# LTC6803.net
KiCad netlist of a schematic drawn in Altium Designer
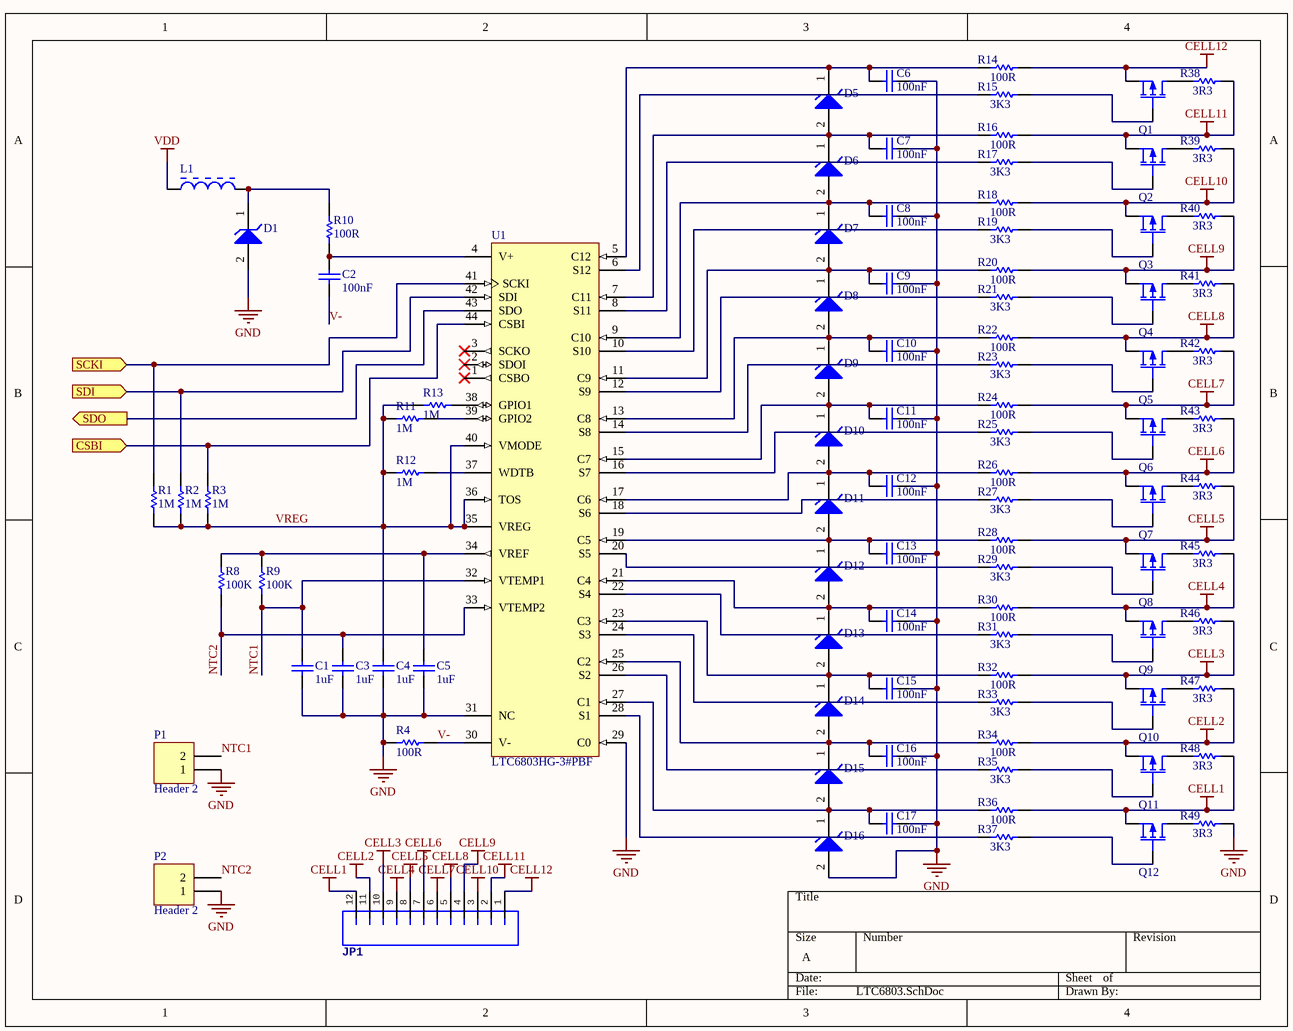
[diagram p0: LTC6803.SchDoc]

(export (version "E")
  (design (tool "Eeschema 10.0.6"))
  (components
    (comp (ref "C1")
      (value "1uF")
      (footprint "CAPC0603(1608)100_N")
      (description "CAP 1uF 6.3V Â±10% 0603 (1608 Metric) Thickness 1mm SMD")
      (fields (field (name "TOLERANCE") "Â±10%"))
      (libsource (lib "Altium Content Vault") (part "CAP"))
    )
    (comp (ref "C2")
      (value "100nF")
      (footprint "CAPC0603(1608)100_L")
      (description "CAP 100nF 100V Â±10% 0603 (1608 Metric) Thickness 1mm SMD")
      (fields (field (name "TOLERANCE") "Â±10%"))
      (libsource (lib "Altium Content Vault") (part "CAP"))
    )
    (comp (ref "C3")
      (value "1uF")
      (footprint "CAPC0603(1608)100_N")
      (description "CAP 1uF 6.3V Â±10% 0603 (1608 Metric) Thickness 1mm SMD")
      (fields (field (name "TOLERANCE") "Â±10%"))
      (libsource (lib "Altium Content Vault") (part "CAP"))
    )
    (comp (ref "C4")
      (value "1uF")
      (footprint "CAPC0603(1608)100_N")
      (description "CAP 1uF 6.3V Â±10% 0603 (1608 Metric) Thickness 1mm SMD")
      (fields (field (name "TOLERANCE") "Â±10%"))
      (libsource (lib "Altium Content Vault") (part "CAP"))
    )
    (comp (ref "C5")
      (value "1uF")
      (footprint "CAPC0603(1608)100_N")
      (description "CAP 1uF 6.3V Â±10% 0603 (1608 Metric) Thickness 1mm SMD")
      (fields (field (name "TOLERANCE") "Â±10%"))
      (libsource (lib "Altium Content Vault") (part "CAP"))
    )
    (comp (ref "C6")
      (value "100nF")
      (footprint "CAPC0603(1608)100_M")
      (description "CAP 100nF 6.3V Â±5% 0603 (1608 Metric) Thickness 1mm SMD")
      (fields (field (name "TOLERANCE") "Â±5%"))
      (libsource (lib "Altium Content Vault") (part "CAP"))
    )
    (comp (ref "C7")
      (value "100nF")
      (footprint "CAPC0603(1608)100_M")
      (description "CAP 100nF 6.3V Â±5% 0603 (1608 Metric) Thickness 1mm SMD")
      (fields (field (name "TOLERANCE") "Â±5%"))
      (libsource (lib "Altium Content Vault") (part "CAP"))
    )
    (comp (ref "C8")
      (value "100nF")
      (footprint "CAPC0603(1608)100_M")
      (description "CAP 100nF 6.3V Â±5% 0603 (1608 Metric) Thickness 1mm SMD")
      (fields (field (name "TOLERANCE") "Â±5%"))
      (libsource (lib "Altium Content Vault") (part "CAP"))
    )
    (comp (ref "C9")
      (value "100nF")
      (footprint "CAPC0603(1608)100_M")
      (description "CAP 100nF 6.3V Â±5% 0603 (1608 Metric) Thickness 1mm SMD")
      (fields (field (name "TOLERANCE") "Â±5%"))
      (libsource (lib "Altium Content Vault") (part "CAP"))
    )
    (comp (ref "C10")
      (value "100nF")
      (footprint "CAPC0603(1608)100_M")
      (description "CAP 100nF 6.3V Â±5% 0603 (1608 Metric) Thickness 1mm SMD")
      (fields (field (name "TOLERANCE") "Â±5%"))
      (libsource (lib "Altium Content Vault") (part "CAP"))
    )
    (comp (ref "C11")
      (value "100nF")
      (footprint "CAPC0603(1608)100_M")
      (description "CAP 100nF 6.3V Â±5% 0603 (1608 Metric) Thickness 1mm SMD")
      (fields (field (name "TOLERANCE") "Â±5%"))
      (libsource (lib "Altium Content Vault") (part "CAP"))
    )
    (comp (ref "C12")
      (value "100nF")
      (footprint "CAPC0603(1608)100_M")
      (description "CAP 100nF 6.3V Â±5% 0603 (1608 Metric) Thickness 1mm SMD")
      (fields (field (name "TOLERANCE") "Â±5%"))
      (libsource (lib "Altium Content Vault") (part "CAP"))
    )
    (comp (ref "C13")
      (value "100nF")
      (footprint "CAPC0603(1608)100_M")
      (description "CAP 100nF 6.3V Â±5% 0603 (1608 Metric) Thickness 1mm SMD")
      (fields (field (name "TOLERANCE") "Â±5%"))
      (libsource (lib "Altium Content Vault") (part "CAP"))
    )
    (comp (ref "C14")
      (value "100nF")
      (footprint "CAPC0603(1608)100_M")
      (description "CAP 100nF 6.3V Â±5% 0603 (1608 Metric) Thickness 1mm SMD")
      (fields (field (name "TOLERANCE") "Â±5%"))
      (libsource (lib "Altium Content Vault") (part "CAP"))
    )
    (comp (ref "C15")
      (value "100nF")
      (footprint "CAPC0603(1608)100_M")
      (description "CAP 100nF 6.3V Â±5% 0603 (1608 Metric) Thickness 1mm SMD")
      (fields (field (name "TOLERANCE") "Â±5%"))
      (libsource (lib "Altium Content Vault") (part "CAP"))
    )
    (comp (ref "C16")
      (value "100nF")
      (footprint "CAPC0603(1608)100_M")
      (description "CAP 100nF 6.3V Â±5% 0603 (1608 Metric) Thickness 1mm SMD")
      (fields (field (name "TOLERANCE") "Â±5%"))
      (libsource (lib "Altium Content Vault") (part "CAP"))
    )
    (comp (ref "C17")
      (value "100nF")
      (footprint "CAPC0603(1608)100_M")
      (description "CAP 100nF 6.3V Â±5% 0603 (1608 Metric) Thickness 1mm SMD")
      (fields (field (name "TOLERANCE") "Â±5%"))
      (libsource (lib "Altium Content Vault") (part "CAP"))
    )
    (comp (ref "D1") (value "~") (footprint "SOD-123") (libsource (lib "Components") (part "CMHZ5265B")))
    (comp (ref "D5")
      (value "~")
      (footprint "ONSC-SOD-323-2-477-02_V")
      (description "Zener Voltage Regulator, 300 mW, 2-Pin SOD-323, Tape and Reel")
      (fields (field (name "MANUFACTURER") "On Semiconductor") (field (name "PARTNUMBER") "MM3Z12VT1"))
      (libsource (lib "Altium Content Vault") (part "ONSC-K1A2-2"))
    )
    (comp (ref "D6")
      (value "~")
      (footprint "ONSC-SOD-323-2-477-02_V")
      (description "Zener Voltage Regulator, 300 mW, 2-Pin SOD-323, Tape and Reel")
      (fields (field (name "MANUFACTURER") "On Semiconductor") (field (name "PARTNUMBER") "MM3Z12VT1"))
      (libsource (lib "Altium Content Vault") (part "ONSC-K1A2-2"))
    )
    (comp (ref "D7")
      (value "~")
      (footprint "ONSC-SOD-323-2-477-02_V")
      (description "Zener Voltage Regulator, 300 mW, 2-Pin SOD-323, Tape and Reel")
      (fields (field (name "MANUFACTURER") "On Semiconductor") (field (name "PARTNUMBER") "MM3Z12VT1"))
      (libsource (lib "Altium Content Vault") (part "ONSC-K1A2-2"))
    )
    (comp (ref "D8")
      (value "~")
      (footprint "ONSC-SOD-323-2-477-02_V")
      (description "Zener Voltage Regulator, 300 mW, 2-Pin SOD-323, Tape and Reel")
      (fields (field (name "MANUFACTURER") "On Semiconductor") (field (name "PARTNUMBER") "MM3Z12VT1"))
      (libsource (lib "Altium Content Vault") (part "ONSC-K1A2-2"))
    )
    (comp (ref "D9")
      (value "~")
      (footprint "ONSC-SOD-323-2-477-02_V")
      (description "Zener Voltage Regulator, 300 mW, 2-Pin SOD-323, Tape and Reel")
      (fields (field (name "MANUFACTURER") "On Semiconductor") (field (name "PARTNUMBER") "MM3Z12VT1"))
      (libsource (lib "Altium Content Vault") (part "ONSC-K1A2-2"))
    )
    (comp (ref "D10")
      (value "~")
      (footprint "ONSC-SOD-323-2-477-02_V")
      (description "Zener Voltage Regulator, 300 mW, 2-Pin SOD-323, Tape and Reel")
      (fields (field (name "MANUFACTURER") "On Semiconductor") (field (name "PARTNUMBER") "MM3Z12VT1"))
      (libsource (lib "Altium Content Vault") (part "ONSC-K1A2-2"))
    )
    (comp (ref "D11")
      (value "~")
      (footprint "ONSC-SOD-323-2-477-02_V")
      (description "Zener Voltage Regulator, 300 mW, 2-Pin SOD-323, Tape and Reel")
      (fields (field (name "MANUFACTURER") "On Semiconductor") (field (name "PARTNUMBER") "MM3Z12VT1"))
      (libsource (lib "Altium Content Vault") (part "ONSC-K1A2-2"))
    )
    (comp (ref "D12")
      (value "~")
      (footprint "ONSC-SOD-323-2-477-02_V")
      (description "Zener Voltage Regulator, 300 mW, 2-Pin SOD-323, Tape and Reel")
      (fields (field (name "MANUFACTURER") "On Semiconductor") (field (name "PARTNUMBER") "MM3Z12VT1"))
      (libsource (lib "Altium Content Vault") (part "ONSC-K1A2-2"))
    )
    (comp (ref "D13")
      (value "~")
      (footprint "ONSC-SOD-323-2-477-02_V")
      (description "Zener Voltage Regulator, 300 mW, 2-Pin SOD-323, Tape and Reel")
      (fields (field (name "MANUFACTURER") "On Semiconductor") (field (name "PARTNUMBER") "MM3Z12VT1"))
      (libsource (lib "Altium Content Vault") (part "ONSC-K1A2-2"))
    )
    (comp (ref "D14")
      (value "~")
      (footprint "ONSC-SOD-323-2-477-02_V")
      (description "Zener Voltage Regulator, 300 mW, 2-Pin SOD-323, Tape and Reel")
      (fields (field (name "MANUFACTURER") "On Semiconductor") (field (name "PARTNUMBER") "MM3Z12VT1"))
      (libsource (lib "Altium Content Vault") (part "ONSC-K1A2-2"))
    )
    (comp (ref "D15")
      (value "~")
      (footprint "ONSC-SOD-323-2-477-02_V")
      (description "Zener Voltage Regulator, 300 mW, 2-Pin SOD-323, Tape and Reel")
      (fields (field (name "MANUFACTURER") "On Semiconductor") (field (name "PARTNUMBER") "MM3Z12VT1"))
      (libsource (lib "Altium Content Vault") (part "ONSC-K1A2-2"))
    )
    (comp (ref "D16")
      (value "~")
      (footprint "ONSC-SOD-323-2-477-02_V")
      (description "Zener Voltage Regulator, 300 mW, 2-Pin SOD-323, Tape and Reel")
      (fields (field (name "MANUFACTURER") "On Semiconductor") (field (name "PARTNUMBER") "MM3Z12VT1"))
      (libsource (lib "Altium Content Vault") (part "ONSC-K1A2-2"))
    )
    (comp (ref "JP1")
      (value "~")
      (footprint "JST-6-PTH-VERT")
      (libsource (lib "Components") (part "JST_12_RIGHT"))
    )
    (comp (ref "L1")
      (value "~")
      (footprint "MURA-BLM31-B60-CHIP-2_V3")
      (libsource (lib "Components") (part "MURA-FB-2"))
    )
    (comp (ref "P1")
      (value "Header 2")
      (footprint "HDR1X2")
      (description "Header, 2-Pin")
      (fields (field (name "PUBLISHER") "Altium Limited"))
      (libsource (lib "Miscellaneous Connectors") (part "Header 2"))
    )
    (comp (ref "P2")
      (value "Header 2")
      (footprint "HDR1X2")
      (description "Header, 2-Pin")
      (fields (field (name "PUBLISHER") "Altium Limited"))
      (libsource (lib "Miscellaneous Connectors") (part "Header 2"))
    )
    (comp (ref "Q1")
      (value "MOSFET-P")
      (footprint "SOT23-3")
      (description "P-Channel MOSFET")
      (fields (field (name "PUBLISHER") "Altium Limited"))
      (libsource (lib "Components") (part "MOSFET-P"))
    )
    (comp (ref "Q2")
      (value "MOSFET-P")
      (footprint "SOT23-3")
      (description "P-Channel MOSFET")
      (fields (field (name "PUBLISHER") "Altium Limited"))
      (libsource (lib "Components") (part "MOSFET-P"))
    )
    (comp (ref "Q3")
      (value "MOSFET-P")
      (footprint "SOT23-3")
      (description "P-Channel MOSFET")
      (fields (field (name "PUBLISHER") "Altium Limited"))
      (libsource (lib "Components") (part "MOSFET-P"))
    )
    (comp (ref "Q4")
      (value "MOSFET-P")
      (footprint "SOT23-3")
      (description "P-Channel MOSFET")
      (fields (field (name "PUBLISHER") "Altium Limited"))
      (libsource (lib "Components") (part "MOSFET-P"))
    )
    (comp (ref "Q5")
      (value "MOSFET-P")
      (footprint "SOT23-3")
      (description "P-Channel MOSFET")
      (fields (field (name "PUBLISHER") "Altium Limited"))
      (libsource (lib "Components") (part "MOSFET-P"))
    )
    (comp (ref "Q6")
      (value "MOSFET-P")
      (footprint "SOT23-3")
      (description "P-Channel MOSFET")
      (fields (field (name "PUBLISHER") "Altium Limited"))
      (libsource (lib "Components") (part "MOSFET-P"))
    )
    (comp (ref "Q7")
      (value "MOSFET-P")
      (footprint "SOT23-3")
      (description "P-Channel MOSFET")
      (fields (field (name "PUBLISHER") "Altium Limited"))
      (libsource (lib "Components") (part "MOSFET-P"))
    )
    (comp (ref "Q8")
      (value "MOSFET-P")
      (footprint "SOT23-3")
      (description "P-Channel MOSFET")
      (fields (field (name "PUBLISHER") "Altium Limited"))
      (libsource (lib "Components") (part "MOSFET-P"))
    )
    (comp (ref "Q9")
      (value "MOSFET-P")
      (footprint "SOT23-3")
      (description "P-Channel MOSFET")
      (fields (field (name "PUBLISHER") "Altium Limited"))
      (libsource (lib "Components") (part "MOSFET-P"))
    )
    (comp (ref "Q10")
      (value "MOSFET-P")
      (footprint "SOT23-3")
      (description "P-Channel MOSFET")
      (fields (field (name "PUBLISHER") "Altium Limited"))
      (libsource (lib "Components") (part "MOSFET-P"))
    )
    (comp (ref "Q11")
      (value "MOSFET-P")
      (footprint "SOT23-3")
      (description "P-Channel MOSFET")
      (fields (field (name "PUBLISHER") "Altium Limited"))
      (libsource (lib "Components") (part "MOSFET-P"))
    )
    (comp (ref "Q12")
      (value "MOSFET-P")
      (footprint "SOT23-3")
      (description "P-Channel MOSFET")
      (fields (field (name "PUBLISHER") "Altium Limited"))
      (libsource (lib "Components") (part "MOSFET-P"))
    )
    (comp (ref "R1")
      (value "1M")
      (footprint "RESC0603(1608)_L")
      (description "1M 0.1W 1% 0603 (1608 Metric)  SMD")
      (fields (field (name "POWER") "0.1 W") (field (name "TOLERANCE") "1 %"))
      (libsource (lib "Altium Content Vault") (part "RES"))
    )
    (comp (ref "R2")
      (value "1M")
      (footprint "RESC0603(1608)_L")
      (description "1M 0.1W 1% 0603 (1608 Metric)  SMD")
      (fields (field (name "POWER") "0.1 W") (field (name "TOLERANCE") "1 %"))
      (libsource (lib "Altium Content Vault") (part "RES"))
    )
    (comp (ref "R3")
      (value "1M")
      (footprint "RESC0603(1608)_L")
      (description "1M 0.1W 1% 0603 (1608 Metric)  SMD")
      (fields (field (name "POWER") "0.1 W") (field (name "TOLERANCE") "1 %"))
      (libsource (lib "Altium Content Vault") (part "RES"))
    )
    (comp (ref "R4")
      (value "100R")
      (footprint "RESC0603(1608)_L")
      (description "100R 0.1W 5% 0603 (1608 Metric)  SMD")
      (fields (field (name "TOLERANCE") "5 %") (field (name "POWER") "0.1 W"))
      (libsource (lib "Altium Content Vault") (part "RES"))
    )
    (comp (ref "R8")
      (value "100K")
      (footprint "RESC0603(1608)_N")
      (description "100K 0.1W 5% 0603 (1608 Metric)  SMD")
      (fields (field (name "TOLERANCE") "5 %") (field (name "POWER") "0.1 W"))
      (libsource (lib "Altium Content Vault") (part "RES"))
    )
    (comp (ref "R9")
      (value "100K")
      (footprint "RESC0603(1608)_N")
      (description "100K 0.1W 5% 0603 (1608 Metric)  SMD")
      (fields (field (name "TOLERANCE") "5 %") (field (name "POWER") "0.1 W"))
      (libsource (lib "Altium Content Vault") (part "RES"))
    )
    (comp (ref "R10")
      (value "100R")
      (footprint "RESC0603(1608)_L")
      (description "100R 0.1W 5% 0603 (1608 Metric)  SMD")
      (fields (field (name "TOLERANCE") "5 %") (field (name "POWER") "0.1 W"))
      (libsource (lib "Altium Content Vault") (part "CMP-1012-00050-1"))
    )
    (comp (ref "R11")
      (value "1M")
      (footprint "RESC0603(1608)_L")
      (description "1M 0.1W 1% 0603 (1608 Metric)  SMD")
      (fields (field (name "POWER") "0.1 W") (field (name "TOLERANCE") "1 %"))
      (libsource (lib "Altium Content Vault") (part "RES"))
    )
    (comp (ref "R12")
      (value "1M")
      (footprint "RESC0603(1608)_L")
      (description "1M 0.1W 1% 0603 (1608 Metric)  SMD")
      (fields (field (name "POWER") "0.1 W") (field (name "TOLERANCE") "1 %"))
      (libsource (lib "Altium Content Vault") (part "RES"))
    )
    (comp (ref "R13")
      (value "1M")
      (footprint "RESC0603(1608)_L")
      (description "1M 0.1W 1% 0603 (1608 Metric)  SMD")
      (fields (field (name "POWER") "0.1 W") (field (name "TOLERANCE") "1 %"))
      (libsource (lib "Altium Content Vault") (part "RES"))
    )
    (comp (ref "R14")
      (value "100R")
      (footprint "RESC0603(1608)_N")
      (description "100R 0.1W 5% 0603 (1608 Metric)  SMD")
      (fields (field (name "TOLERANCE") "5 %") (field (name "POWER") "0.1 W"))
      (libsource (lib "Altium Content Vault") (part "CMP-1012-00050-1"))
    )
    (comp (ref "R15")
      (value "3K3")
      (footprint "RESC0603(1608)_N")
      (description "3K3 0.1W 5% 0603 (1608 Metric)  SMD")
      (fields (field (name "TOLERANCE") "5 %") (field (name "POWER") "0.1 W"))
      (libsource (lib "Altium Content Vault") (part "RES"))
    )
    (comp (ref "R16")
      (value "100R")
      (footprint "RESC0603(1608)_N")
      (description "100R 0.1W 5% 0603 (1608 Metric)  SMD")
      (fields (field (name "TOLERANCE") "5 %") (field (name "POWER") "0.1 W"))
      (libsource (lib "Altium Content Vault") (part "CMP-1012-00050-1"))
    )
    (comp (ref "R17")
      (value "3K3")
      (footprint "RESC0603(1608)_N")
      (description "3K3 0.1W 5% 0603 (1608 Metric)  SMD")
      (fields (field (name "TOLERANCE") "5 %") (field (name "POWER") "0.1 W"))
      (libsource (lib "Altium Content Vault") (part "RES"))
    )
    (comp (ref "R18")
      (value "100R")
      (footprint "RESC0603(1608)_N")
      (description "100R 0.1W 5% 0603 (1608 Metric)  SMD")
      (fields (field (name "TOLERANCE") "5 %") (field (name "POWER") "0.1 W"))
      (libsource (lib "Altium Content Vault") (part "CMP-1012-00050-1"))
    )
    (comp (ref "R19")
      (value "3K3")
      (footprint "RESC0603(1608)_N")
      (description "3K3 0.1W 5% 0603 (1608 Metric)  SMD")
      (fields (field (name "TOLERANCE") "5 %") (field (name "POWER") "0.1 W"))
      (libsource (lib "Altium Content Vault") (part "RES"))
    )
    (comp (ref "R20")
      (value "100R")
      (footprint "RESC0603(1608)_N")
      (description "100R 0.1W 5% 0603 (1608 Metric)  SMD")
      (fields (field (name "TOLERANCE") "5 %") (field (name "POWER") "0.1 W"))
      (libsource (lib "Altium Content Vault") (part "CMP-1012-00050-1"))
    )
    (comp (ref "R21")
      (value "3K3")
      (footprint "RESC0603(1608)_N")
      (description "3K3 0.1W 5% 0603 (1608 Metric)  SMD")
      (fields (field (name "TOLERANCE") "5 %") (field (name "POWER") "0.1 W"))
      (libsource (lib "Altium Content Vault") (part "RES"))
    )
    (comp (ref "R22")
      (value "100R")
      (footprint "RESC0603(1608)_N")
      (description "100R 0.1W 5% 0603 (1608 Metric)  SMD")
      (fields (field (name "TOLERANCE") "5 %") (field (name "POWER") "0.1 W"))
      (libsource (lib "Altium Content Vault") (part "CMP-1012-00050-1"))
    )
    (comp (ref "R23")
      (value "3K3")
      (footprint "RESC0603(1608)_N")
      (description "3K3 0.1W 5% 0603 (1608 Metric)  SMD")
      (fields (field (name "TOLERANCE") "5 %") (field (name "POWER") "0.1 W"))
      (libsource (lib "Altium Content Vault") (part "RES"))
    )
    (comp (ref "R24")
      (value "100R")
      (footprint "RESC0603(1608)_N")
      (description "100R 0.1W 5% 0603 (1608 Metric)  SMD")
      (fields (field (name "TOLERANCE") "5 %") (field (name "POWER") "0.1 W"))
      (libsource (lib "Altium Content Vault") (part "CMP-1012-00050-1"))
    )
    (comp (ref "R25")
      (value "3K3")
      (footprint "RESC0603(1608)_N")
      (description "3K3 0.1W 5% 0603 (1608 Metric)  SMD")
      (fields (field (name "TOLERANCE") "5 %") (field (name "POWER") "0.1 W"))
      (libsource (lib "Altium Content Vault") (part "RES"))
    )
    (comp (ref "R26")
      (value "100R")
      (footprint "RESC0603(1608)_N")
      (description "100R 0.1W 5% 0603 (1608 Metric)  SMD")
      (fields (field (name "TOLERANCE") "5 %") (field (name "POWER") "0.1 W"))
      (libsource (lib "Altium Content Vault") (part "CMP-1012-00050-1"))
    )
    (comp (ref "R27")
      (value "3K3")
      (footprint "RESC0603(1608)_N")
      (description "3K3 0.1W 5% 0603 (1608 Metric)  SMD")
      (fields (field (name "TOLERANCE") "5 %") (field (name "POWER") "0.1 W"))
      (libsource (lib "Altium Content Vault") (part "RES"))
    )
    (comp (ref "R28")
      (value "100R")
      (footprint "RESC0603(1608)_N")
      (description "100R 0.1W 5% 0603 (1608 Metric)  SMD")
      (fields (field (name "TOLERANCE") "5 %") (field (name "POWER") "0.1 W"))
      (libsource (lib "Altium Content Vault") (part "CMP-1012-00050-1"))
    )
    (comp (ref "R29")
      (value "3K3")
      (footprint "RESC0603(1608)_N")
      (description "3K3 0.1W 5% 0603 (1608 Metric)  SMD")
      (fields (field (name "TOLERANCE") "5 %") (field (name "POWER") "0.1 W"))
      (libsource (lib "Altium Content Vault") (part "RES"))
    )
    (comp (ref "R30")
      (value "100R")
      (footprint "RESC0603(1608)_N")
      (description "100R 0.1W 5% 0603 (1608 Metric)  SMD")
      (fields (field (name "TOLERANCE") "5 %") (field (name "POWER") "0.1 W"))
      (libsource (lib "Altium Content Vault") (part "CMP-1012-00050-1"))
    )
    (comp (ref "R31")
      (value "3K3")
      (footprint "RESC0603(1608)_N")
      (description "3K3 0.1W 5% 0603 (1608 Metric)  SMD")
      (fields (field (name "TOLERANCE") "5 %") (field (name "POWER") "0.1 W"))
      (libsource (lib "Altium Content Vault") (part "RES"))
    )
    (comp (ref "R32")
      (value "100R")
      (footprint "RESC0603(1608)_N")
      (description "100R 0.1W 5% 0603 (1608 Metric)  SMD")
      (fields (field (name "TOLERANCE") "5 %") (field (name "POWER") "0.1 W"))
      (libsource (lib "Altium Content Vault") (part "CMP-1012-00050-1"))
    )
    (comp (ref "R33")
      (value "3K3")
      (footprint "RESC0603(1608)_N")
      (description "3K3 0.1W 5% 0603 (1608 Metric)  SMD")
      (fields (field (name "TOLERANCE") "5 %") (field (name "POWER") "0.1 W"))
      (libsource (lib "Altium Content Vault") (part "RES"))
    )
    (comp (ref "R34")
      (value "100R")
      (footprint "RESC0603(1608)_N")
      (description "100R 0.1W 5% 0603 (1608 Metric)  SMD")
      (fields (field (name "TOLERANCE") "5 %") (field (name "POWER") "0.1 W"))
      (libsource (lib "Altium Content Vault") (part "CMP-1012-00050-1"))
    )
    (comp (ref "R35")
      (value "3K3")
      (footprint "RESC0603(1608)_N")
      (description "3K3 0.1W 5% 0603 (1608 Metric)  SMD")
      (fields (field (name "TOLERANCE") "5 %") (field (name "POWER") "0.1 W"))
      (libsource (lib "Altium Content Vault") (part "RES"))
    )
    (comp (ref "R36")
      (value "100R")
      (footprint "RESC0603(1608)_N")
      (description "100R 0.1W 5% 0603 (1608 Metric)  SMD")
      (fields (field (name "TOLERANCE") "5 %") (field (name "POWER") "0.1 W"))
      (libsource (lib "Altium Content Vault") (part "CMP-1012-00050-1"))
    )
    (comp (ref "R37")
      (value "3K3")
      (footprint "RESC0603(1608)_N")
      (description "3K3 0.1W 5% 0603 (1608 Metric)  SMD")
      (fields (field (name "TOLERANCE") "5 %") (field (name "POWER") "0.1 W"))
      (libsource (lib "Altium Content Vault") (part "RES"))
    )
    (comp (ref "R38")
      (value "3R3")
      (footprint "RESC2512(6432)_N")
      (description "3R3 1W 5% 2512 (6432 Metric)  SMD")
      (fields (field (name "TOLERANCE") "5 %") (field (name "POWER") "1 W"))
      (libsource (lib "Altium Content Vault") (part "RES"))
    )
    (comp (ref "R39")
      (value "3R3")
      (footprint "RESC2512(6432)_N")
      (description "3R3 1W 5% 2512 (6432 Metric)  SMD")
      (fields (field (name "TOLERANCE") "5 %") (field (name "POWER") "1 W"))
      (libsource (lib "Altium Content Vault") (part "RES"))
    )
    (comp (ref "R40")
      (value "3R3")
      (footprint "RESC2512(6432)_N")
      (description "3R3 1W 5% 2512 (6432 Metric)  SMD")
      (fields (field (name "TOLERANCE") "5 %") (field (name "POWER") "1 W"))
      (libsource (lib "Altium Content Vault") (part "RES"))
    )
    (comp (ref "R41")
      (value "3R3")
      (footprint "RESC2512(6432)_N")
      (description "3R3 1W 5% 2512 (6432 Metric)  SMD")
      (fields (field (name "TOLERANCE") "5 %") (field (name "POWER") "1 W"))
      (libsource (lib "Altium Content Vault") (part "RES"))
    )
    (comp (ref "R42")
      (value "3R3")
      (footprint "RESC2512(6432)_N")
      (description "3R3 1W 5% 2512 (6432 Metric)  SMD")
      (fields (field (name "TOLERANCE") "5 %") (field (name "POWER") "1 W"))
      (libsource (lib "Altium Content Vault") (part "RES"))
    )
    (comp (ref "R43")
      (value "3R3")
      (footprint "RESC2512(6432)_N")
      (description "3R3 1W 5% 2512 (6432 Metric)  SMD")
      (fields (field (name "TOLERANCE") "5 %") (field (name "POWER") "1 W"))
      (libsource (lib "Altium Content Vault") (part "RES"))
    )
    (comp (ref "R44")
      (value "3R3")
      (footprint "RESC2512(6432)_N")
      (description "3R3 1W 5% 2512 (6432 Metric)  SMD")
      (fields (field (name "TOLERANCE") "5 %") (field (name "POWER") "1 W"))
      (libsource (lib "Altium Content Vault") (part "RES"))
    )
    (comp (ref "R45")
      (value "3R3")
      (footprint "RESC2512(6432)_N")
      (description "3R3 1W 5% 2512 (6432 Metric)  SMD")
      (fields (field (name "TOLERANCE") "5 %") (field (name "POWER") "1 W"))
      (libsource (lib "Altium Content Vault") (part "RES"))
    )
    (comp (ref "R46")
      (value "3R3")
      (footprint "RESC2512(6432)_N")
      (description "3R3 1W 5% 2512 (6432 Metric)  SMD")
      (fields (field (name "TOLERANCE") "5 %") (field (name "POWER") "1 W"))
      (libsource (lib "Altium Content Vault") (part "RES"))
    )
    (comp (ref "R47")
      (value "3R3")
      (footprint "RESC2512(6432)_N")
      (description "3R3 1W 5% 2512 (6432 Metric)  SMD")
      (fields (field (name "TOLERANCE") "5 %") (field (name "POWER") "1 W"))
      (libsource (lib "Altium Content Vault") (part "RES"))
    )
    (comp (ref "R48")
      (value "3R3")
      (footprint "RESC2512(6432)_N")
      (description "3R3 1W 5% 2512 (6432 Metric)  SMD")
      (fields (field (name "TOLERANCE") "5 %") (field (name "POWER") "1 W"))
      (libsource (lib "Altium Content Vault") (part "RES"))
    )
    (comp (ref "R49")
      (value "3R3")
      (footprint "RESC2512(6432)_N")
      (description "3R3 1W 5% 2512 (6432 Metric)  SMD")
      (fields (field (name "TOLERANCE") "5 %") (field (name "POWER") "1 W"))
      (libsource (lib "Altium Content Vault") (part "RES"))
    )
    (comp (ref "U1")
      (value "LTC6803HG-3#PBF")
      (footprint "LT-G-44_L")
      (description "Multicell Battery Stack Monitor, 60 V Vin MAX, 44-pin SOP (G-44), -40 to 125 degC, Pb-Free")
      (fields (field (name "MANUFACTURER") "Linear Technology"))
      (libsource (lib "Altium Content Vault") (part "LT-LTC6803-3-G-44"))
    )
  )
  (nets
    (net (code "1") (name "/CSBI") (class "Default")
      (node (ref "R3") (pin "2") (pinfunction "2_2") (pintype "passive"))
      (node (ref "U1") (pin "44") (pinfunction "CSBI_44") (pintype "input"))
    )
    (net (code "2") (name "/NTC1") (class "Default")
      (node (ref "C1") (pin "2") (pinfunction "2_2") (pintype "passive"))
      (node (ref "P1") (pin "2") (pinfunction "2_2") (pintype "passive"))
      (node (ref "R9") (pin "1") (pinfunction "1_1") (pintype "passive"))
      (node (ref "U1") (pin "32") (pinfunction "VTEMP1_32") (pintype "input"))
    )
    (net (code "3") (name "/NTC2") (class "Default")
      (node (ref "C3") (pin "2") (pinfunction "2_2") (pintype "passive"))
      (node (ref "P2") (pin "2") (pinfunction "2_2") (pintype "passive"))
      (node (ref "R8") (pin "1") (pinfunction "1_1") (pintype "passive"))
      (node (ref "U1") (pin "33") (pinfunction "VTEMP2_33") (pintype "input"))
    )
    (net (code "4") (name "/SCKI") (class "Default")
      (node (ref "R1") (pin "2") (pinfunction "2_2") (pintype "passive"))
      (node (ref "U1") (pin "41") (pinfunction "SCKI_41") (pintype "input"))
    )
    (net (code "5") (name "/SDI") (class "Default")
      (node (ref "R2") (pin "2") (pinfunction "2_2") (pintype "passive"))
      (node (ref "U1") (pin "42") (pinfunction "SDI_42") (pintype "input"))
    )
    (net (code "6") (name "/SDO") (class "Default")
      (node (ref "U1") (pin "43") (pinfunction "SDO_43") (pintype "open_collector"))
    )
    (net (code "7") (name "/V-") (class "Default")
      (node (ref "C2") (pin "1") (pinfunction "1_1") (pintype "passive"))
      (node (ref "R4") (pin "2") (pinfunction "2_2") (pintype "passive"))
      (node (ref "U1") (pin "30") (pinfunction "V-_30") (pintype "power_in"))
    )
    (net (code "8") (name "/VREG") (class "Default")
      (node (ref "C4") (pin "2") (pinfunction "2_2") (pintype "passive"))
      (node (ref "R1") (pin "1") (pinfunction "1_1") (pintype "passive"))
      (node (ref "R11") (pin "1") (pinfunction "1_1") (pintype "passive"))
      (node (ref "R12") (pin "1") (pinfunction "1_1") (pintype "passive"))
      (node (ref "R13") (pin "1") (pinfunction "1_1") (pintype "passive"))
      (node (ref "R2") (pin "1") (pinfunction "1_1") (pintype "passive"))
      (node (ref "R3") (pin "1") (pinfunction "1_1") (pintype "passive"))
      (node (ref "U1") (pin "35") (pinfunction "VREG_35") (pintype "power_in"))
      (node (ref "U1") (pin "36") (pinfunction "TOS_36") (pintype "input"))
      (node (ref "U1") (pin "40") (pinfunction "VMODE_40") (pintype "input"))
    )
    (net (code "9") (name "CELL1") (class "Default")
      (node (ref "JP1") (pin "12") (pinfunction "12_12") (pintype "passive"))
      (node (ref "Q12") (pin "3") (pinfunction "S_3") (pintype "passive"))
      (node (ref "R36") (pin "2") (pinfunction "2_2") (pintype "passive"))
      (node (ref "R48") (pin "1") (pinfunction "1_1") (pintype "passive"))
    )
    (net (code "10") (name "CELL2") (class "Default")
      (node (ref "JP1") (pin "11") (pinfunction "11_11") (pintype "passive"))
      (node (ref "Q11") (pin "3") (pinfunction "S_3") (pintype "passive"))
      (node (ref "R34") (pin "2") (pinfunction "2_2") (pintype "passive"))
      (node (ref "R47") (pin "1") (pinfunction "1_1") (pintype "passive"))
    )
    (net (code "11") (name "CELL3") (class "Default")
      (node (ref "JP1") (pin "10") (pinfunction "10_10") (pintype "passive"))
      (node (ref "Q10") (pin "3") (pinfunction "S_3") (pintype "passive"))
      (node (ref "R32") (pin "2") (pinfunction "2_2") (pintype "passive"))
      (node (ref "R46") (pin "1") (pinfunction "1_1") (pintype "passive"))
    )
    (net (code "12") (name "CELL4") (class "Default")
      (node (ref "JP1") (pin "9") (pinfunction "9_9") (pintype "passive"))
      (node (ref "Q9") (pin "3") (pinfunction "S_3") (pintype "passive"))
      (node (ref "R30") (pin "2") (pinfunction "2_2") (pintype "passive"))
      (node (ref "R45") (pin "1") (pinfunction "1_1") (pintype "passive"))
    )
    (net (code "13") (name "CELL5") (class "Default")
      (node (ref "JP1") (pin "8") (pinfunction "8_8") (pintype "passive"))
      (node (ref "Q8") (pin "3") (pinfunction "S_3") (pintype "passive"))
      (node (ref "R28") (pin "2") (pinfunction "2_2") (pintype "passive"))
      (node (ref "R44") (pin "1") (pinfunction "1_1") (pintype "passive"))
    )
    (net (code "14") (name "CELL6") (class "Default")
      (node (ref "JP1") (pin "7") (pinfunction "7_7") (pintype "passive"))
      (node (ref "Q7") (pin "3") (pinfunction "S_3") (pintype "passive"))
      (node (ref "R26") (pin "2") (pinfunction "2_2") (pintype "passive"))
      (node (ref "R43") (pin "1") (pinfunction "1_1") (pintype "passive"))
    )
    (net (code "15") (name "CELL7") (class "Default")
      (node (ref "JP1") (pin "6") (pinfunction "6_6") (pintype "passive"))
      (node (ref "Q6") (pin "3") (pinfunction "S_3") (pintype "passive"))
      (node (ref "R24") (pin "2") (pinfunction "2_2") (pintype "passive"))
      (node (ref "R42") (pin "1") (pinfunction "1_1") (pintype "passive"))
    )
    (net (code "16") (name "CELL8") (class "Default")
      (node (ref "JP1") (pin "5") (pinfunction "5_5") (pintype "passive"))
      (node (ref "Q5") (pin "3") (pinfunction "S_3") (pintype "passive"))
      (node (ref "R22") (pin "2") (pinfunction "2_2") (pintype "passive"))
      (node (ref "R41") (pin "1") (pinfunction "1_1") (pintype "passive"))
    )
    (net (code "17") (name "CELL9") (class "Default")
      (node (ref "JP1") (pin "4") (pinfunction "4_4") (pintype "passive"))
      (node (ref "Q4") (pin "3") (pinfunction "S_3") (pintype "passive"))
      (node (ref "R20") (pin "2") (pinfunction "2_2") (pintype "passive"))
      (node (ref "R40") (pin "1") (pinfunction "1_1") (pintype "passive"))
    )
    (net (code "18") (name "CELL10") (class "Default")
      (node (ref "JP1") (pin "3") (pinfunction "3_3") (pintype "passive"))
      (node (ref "Q3") (pin "3") (pinfunction "S_3") (pintype "passive"))
      (node (ref "R18") (pin "2") (pinfunction "2_2") (pintype "passive"))
      (node (ref "R39") (pin "1") (pinfunction "1_1") (pintype "passive"))
    )
    (net (code "19") (name "CELL11") (class "Default")
      (node (ref "JP1") (pin "2") (pinfunction "2_2") (pintype "passive"))
      (node (ref "Q2") (pin "3") (pinfunction "S_3") (pintype "passive"))
      (node (ref "R16") (pin "2") (pinfunction "2_2") (pintype "passive"))
      (node (ref "R38") (pin "1") (pinfunction "1_1") (pintype "passive"))
    )
    (net (code "20") (name "CELL12") (class "Default")
      (node (ref "JP1") (pin "1") (pinfunction "1_1") (pintype "passive"))
      (node (ref "Q1") (pin "3") (pinfunction "S_3") (pintype "passive"))
      (node (ref "R14") (pin "2") (pinfunction "2_2") (pintype "passive"))
    )
    (net (code "21") (name "GND") (class "Default")
      (node (ref "C1") (pin "1") (pinfunction "1_1") (pintype "passive"))
      (node (ref "C10") (pin "1") (pinfunction "1_1") (pintype "passive"))
      (node (ref "C11") (pin "1") (pinfunction "1_1") (pintype "passive"))
      (node (ref "C12") (pin "1") (pinfunction "1_1") (pintype "passive"))
      (node (ref "C13") (pin "1") (pinfunction "1_1") (pintype "passive"))
      (node (ref "C14") (pin "1") (pinfunction "1_1") (pintype "passive"))
      (node (ref "C15") (pin "1") (pinfunction "1_1") (pintype "passive"))
      (node (ref "C16") (pin "1") (pinfunction "1_1") (pintype "passive"))
      (node (ref "C17") (pin "1") (pinfunction "1_1") (pintype "passive"))
      (node (ref "C3") (pin "1") (pinfunction "1_1") (pintype "passive"))
      (node (ref "C4") (pin "1") (pinfunction "1_1") (pintype "passive"))
      (node (ref "C5") (pin "1") (pinfunction "1_1") (pintype "passive"))
      (node (ref "C6") (pin "1") (pinfunction "1_1") (pintype "passive"))
      (node (ref "C7") (pin "1") (pinfunction "1_1") (pintype "passive"))
      (node (ref "C8") (pin "1") (pinfunction "1_1") (pintype "passive"))
      (node (ref "C9") (pin "1") (pinfunction "1_1") (pintype "passive"))
      (node (ref "D1") (pin "2") (pinfunction "A_2") (pintype "passive"))
      (node (ref "D16") (pin "2") (pinfunction "A_2") (pintype "passive"))
      (node (ref "P1") (pin "1") (pinfunction "1_1") (pintype "passive"))
      (node (ref "P2") (pin "1") (pinfunction "1_1") (pintype "passive"))
      (node (ref "R4") (pin "1") (pinfunction "1_1") (pintype "passive"))
      (node (ref "R49") (pin "1") (pinfunction "1_1") (pintype "passive"))
      (node (ref "U1") (pin "29") (pinfunction "C0_29") (pintype "input"))
      (node (ref "U1") (pin "31") (pinfunction "NC_31") (pintype "passive"))
    )
    (net (code "22") (name "Net-(D1-K)") (class "Default")
      (node (ref "D1") (pin "1") (pinfunction "K_1") (pintype "passive"))
      (node (ref "L1") (pin "2") (pinfunction "2_2") (pintype "passive"))
      (node (ref "R10") (pin "2") (pinfunction "2_2") (pintype "passive"))
    )
    (net (code "23") (name "Net-(D5-A)") (class "Default")
      (node (ref "C7") (pin "2") (pinfunction "2_2") (pintype "passive"))
      (node (ref "D5") (pin "2") (pinfunction "A_2") (pintype "passive"))
      (node (ref "D6") (pin "1") (pinfunction "K_1") (pintype "passive"))
      (node (ref "R16") (pin "1") (pinfunction "1_1") (pintype "passive"))
      (node (ref "U1") (pin "7") (pinfunction "C11_7") (pintype "input"))
    )
    (net (code "24") (name "Net-(D5-K)") (class "Default")
      (node (ref "C6") (pin "2") (pinfunction "2_2") (pintype "passive"))
      (node (ref "D5") (pin "1") (pinfunction "K_1") (pintype "passive"))
      (node (ref "R14") (pin "1") (pinfunction "1_1") (pintype "passive"))
      (node (ref "U1") (pin "5") (pinfunction "C12_5") (pintype "input"))
    )
    (net (code "25") (name "Net-(D6-A)") (class "Default")
      (node (ref "C8") (pin "2") (pinfunction "2_2") (pintype "passive"))
      (node (ref "D6") (pin "2") (pinfunction "A_2") (pintype "passive"))
      (node (ref "D7") (pin "1") (pinfunction "K_1") (pintype "passive"))
      (node (ref "R18") (pin "1") (pinfunction "1_1") (pintype "passive"))
      (node (ref "U1") (pin "9") (pinfunction "C10_9") (pintype "input"))
    )
    (net (code "26") (name "Net-(D7-A)") (class "Default")
      (node (ref "C9") (pin "2") (pinfunction "2_2") (pintype "passive"))
      (node (ref "D7") (pin "2") (pinfunction "A_2") (pintype "passive"))
      (node (ref "D8") (pin "1") (pinfunction "K_1") (pintype "passive"))
      (node (ref "R20") (pin "1") (pinfunction "1_1") (pintype "passive"))
      (node (ref "U1") (pin "11") (pinfunction "C9_11") (pintype "input"))
    )
    (net (code "27") (name "Net-(D8-A)") (class "Default")
      (node (ref "C10") (pin "2") (pinfunction "2_2") (pintype "passive"))
      (node (ref "D8") (pin "2") (pinfunction "A_2") (pintype "passive"))
      (node (ref "D9") (pin "1") (pinfunction "K_1") (pintype "passive"))
      (node (ref "R22") (pin "1") (pinfunction "1_1") (pintype "passive"))
      (node (ref "U1") (pin "13") (pinfunction "C8_13") (pintype "input"))
    )
    (net (code "28") (name "Net-(D10-A)") (class "Default")
      (node (ref "C12") (pin "2") (pinfunction "2_2") (pintype "passive"))
      (node (ref "D10") (pin "2") (pinfunction "A_2") (pintype "passive"))
      (node (ref "D11") (pin "1") (pinfunction "K_1") (pintype "passive"))
      (node (ref "R26") (pin "1") (pinfunction "1_1") (pintype "passive"))
      (node (ref "U1") (pin "17") (pinfunction "C6_17") (pintype "input"))
    )
    (net (code "29") (name "Net-(D10-K)") (class "Default")
      (node (ref "C11") (pin "2") (pinfunction "2_2") (pintype "passive"))
      (node (ref "D10") (pin "1") (pinfunction "K_1") (pintype "passive"))
      (node (ref "D9") (pin "2") (pinfunction "A_2") (pintype "passive"))
      (node (ref "R24") (pin "1") (pinfunction "1_1") (pintype "passive"))
      (node (ref "U1") (pin "15") (pinfunction "C7_15") (pintype "input"))
    )
    (net (code "30") (name "Net-(D11-A)") (class "Default")
      (node (ref "C13") (pin "2") (pinfunction "2_2") (pintype "passive"))
      (node (ref "D11") (pin "2") (pinfunction "A_2") (pintype "passive"))
      (node (ref "D12") (pin "1") (pinfunction "K_1") (pintype "passive"))
      (node (ref "R28") (pin "1") (pinfunction "1_1") (pintype "passive"))
      (node (ref "U1") (pin "19") (pinfunction "C5_19") (pintype "input"))
    )
    (net (code "31") (name "Net-(D12-A)") (class "Default")
      (node (ref "C14") (pin "2") (pinfunction "2_2") (pintype "passive"))
      (node (ref "D12") (pin "2") (pinfunction "A_2") (pintype "passive"))
      (node (ref "D13") (pin "1") (pinfunction "K_1") (pintype "passive"))
      (node (ref "R30") (pin "1") (pinfunction "1_1") (pintype "passive"))
      (node (ref "U1") (pin "21") (pinfunction "C4_21") (pintype "input"))
    )
    (net (code "32") (name "Net-(D13-A)") (class "Default")
      (node (ref "C15") (pin "2") (pinfunction "2_2") (pintype "passive"))
      (node (ref "D13") (pin "2") (pinfunction "A_2") (pintype "passive"))
      (node (ref "D14") (pin "1") (pinfunction "K_1") (pintype "passive"))
      (node (ref "R32") (pin "1") (pinfunction "1_1") (pintype "passive"))
      (node (ref "U1") (pin "23") (pinfunction "C3_23") (pintype "input"))
    )
    (net (code "33") (name "Net-(D14-A)") (class "Default")
      (node (ref "C16") (pin "2") (pinfunction "2_2") (pintype "passive"))
      (node (ref "D14") (pin "2") (pinfunction "A_2") (pintype "passive"))
      (node (ref "D15") (pin "1") (pinfunction "K_1") (pintype "passive"))
      (node (ref "R34") (pin "1") (pinfunction "1_1") (pintype "passive"))
      (node (ref "U1") (pin "25") (pinfunction "C2_25") (pintype "input"))
    )
    (net (code "34") (name "Net-(D15-A)") (class "Default")
      (node (ref "C17") (pin "2") (pinfunction "2_2") (pintype "passive"))
      (node (ref "D15") (pin "2") (pinfunction "A_2") (pintype "passive"))
      (node (ref "D16") (pin "1") (pinfunction "K_1") (pintype "passive"))
      (node (ref "R36") (pin "1") (pinfunction "1_1") (pintype "passive"))
      (node (ref "U1") (pin "27") (pinfunction "C1_27") (pintype "input"))
    )
    (net (code "35") (name "Net-(Q1-D)") (class "Default")
      (node (ref "Q1") (pin "2") (pinfunction "D_2") (pintype "passive"))
      (node (ref "R38") (pin "2") (pinfunction "2_2") (pintype "passive"))
    )
    (net (code "36") (name "Net-(Q1-G)") (class "Default")
      (node (ref "Q1") (pin "1") (pinfunction "G_1") (pintype "passive"))
      (node (ref "R15") (pin "2") (pinfunction "2_2") (pintype "passive"))
    )
    (net (code "37") (name "Net-(Q2-D)") (class "Default")
      (node (ref "Q2") (pin "2") (pinfunction "D_2") (pintype "passive"))
      (node (ref "R39") (pin "2") (pinfunction "2_2") (pintype "passive"))
    )
    (net (code "38") (name "Net-(Q2-G)") (class "Default")
      (node (ref "Q2") (pin "1") (pinfunction "G_1") (pintype "passive"))
      (node (ref "R17") (pin "2") (pinfunction "2_2") (pintype "passive"))
    )
    (net (code "39") (name "Net-(Q3-D)") (class "Default")
      (node (ref "Q3") (pin "2") (pinfunction "D_2") (pintype "passive"))
      (node (ref "R40") (pin "2") (pinfunction "2_2") (pintype "passive"))
    )
    (net (code "40") (name "Net-(Q3-G)") (class "Default")
      (node (ref "Q3") (pin "1") (pinfunction "G_1") (pintype "passive"))
      (node (ref "R19") (pin "2") (pinfunction "2_2") (pintype "passive"))
    )
    (net (code "41") (name "Net-(Q4-D)") (class "Default")
      (node (ref "Q4") (pin "2") (pinfunction "D_2") (pintype "passive"))
      (node (ref "R41") (pin "2") (pinfunction "2_2") (pintype "passive"))
    )
    (net (code "42") (name "Net-(Q4-G)") (class "Default")
      (node (ref "Q4") (pin "1") (pinfunction "G_1") (pintype "passive"))
      (node (ref "R21") (pin "2") (pinfunction "2_2") (pintype "passive"))
    )
    (net (code "43") (name "Net-(Q5-D)") (class "Default")
      (node (ref "Q5") (pin "2") (pinfunction "D_2") (pintype "passive"))
      (node (ref "R42") (pin "2") (pinfunction "2_2") (pintype "passive"))
    )
    (net (code "44") (name "Net-(Q5-G)") (class "Default")
      (node (ref "Q5") (pin "1") (pinfunction "G_1") (pintype "passive"))
      (node (ref "R23") (pin "2") (pinfunction "2_2") (pintype "passive"))
    )
    (net (code "45") (name "Net-(Q6-D)") (class "Default")
      (node (ref "Q6") (pin "2") (pinfunction "D_2") (pintype "passive"))
      (node (ref "R43") (pin "2") (pinfunction "2_2") (pintype "passive"))
    )
    (net (code "46") (name "Net-(Q6-G)") (class "Default")
      (node (ref "Q6") (pin "1") (pinfunction "G_1") (pintype "passive"))
      (node (ref "R25") (pin "2") (pinfunction "2_2") (pintype "passive"))
    )
    (net (code "47") (name "Net-(Q7-D)") (class "Default")
      (node (ref "Q7") (pin "2") (pinfunction "D_2") (pintype "passive"))
      (node (ref "R44") (pin "2") (pinfunction "2_2") (pintype "passive"))
    )
    (net (code "48") (name "Net-(Q7-G)") (class "Default")
      (node (ref "Q7") (pin "1") (pinfunction "G_1") (pintype "passive"))
      (node (ref "R27") (pin "2") (pinfunction "2_2") (pintype "passive"))
    )
    (net (code "49") (name "Net-(Q8-D)") (class "Default")
      (node (ref "Q8") (pin "2") (pinfunction "D_2") (pintype "passive"))
      (node (ref "R45") (pin "2") (pinfunction "2_2") (pintype "passive"))
    )
    (net (code "50") (name "Net-(Q8-G)") (class "Default")
      (node (ref "Q8") (pin "1") (pinfunction "G_1") (pintype "passive"))
      (node (ref "R29") (pin "2") (pinfunction "2_2") (pintype "passive"))
    )
    (net (code "51") (name "Net-(Q9-D)") (class "Default")
      (node (ref "Q9") (pin "2") (pinfunction "D_2") (pintype "passive"))
      (node (ref "R46") (pin "2") (pinfunction "2_2") (pintype "passive"))
    )
    (net (code "52") (name "Net-(Q9-G)") (class "Default")
      (node (ref "Q9") (pin "1") (pinfunction "G_1") (pintype "passive"))
      (node (ref "R31") (pin "2") (pinfunction "2_2") (pintype "passive"))
    )
    (net (code "53") (name "Net-(Q10-D)") (class "Default")
      (node (ref "Q10") (pin "2") (pinfunction "D_2") (pintype "passive"))
      (node (ref "R47") (pin "2") (pinfunction "2_2") (pintype "passive"))
    )
    (net (code "54") (name "Net-(Q10-G)") (class "Default")
      (node (ref "Q10") (pin "1") (pinfunction "G_1") (pintype "passive"))
      (node (ref "R33") (pin "2") (pinfunction "2_2") (pintype "passive"))
    )
    (net (code "55") (name "Net-(Q11-D)") (class "Default")
      (node (ref "Q11") (pin "2") (pinfunction "D_2") (pintype "passive"))
      (node (ref "R48") (pin "2") (pinfunction "2_2") (pintype "passive"))
    )
    (net (code "56") (name "Net-(Q11-G)") (class "Default")
      (node (ref "Q11") (pin "1") (pinfunction "G_1") (pintype "passive"))
      (node (ref "R35") (pin "2") (pinfunction "2_2") (pintype "passive"))
    )
    (net (code "57") (name "Net-(Q12-D)") (class "Default")
      (node (ref "Q12") (pin "2") (pinfunction "D_2") (pintype "passive"))
      (node (ref "R49") (pin "2") (pinfunction "2_2") (pintype "passive"))
    )
    (net (code "58") (name "Net-(Q12-G)") (class "Default")
      (node (ref "Q12") (pin "1") (pinfunction "G_1") (pintype "passive"))
      (node (ref "R37") (pin "2") (pinfunction "2_2") (pintype "passive"))
    )
    (net (code "59") (name "Net-(U1-GPIO1)") (class "Default")
      (node (ref "R13") (pin "2") (pinfunction "2_2") (pintype "passive"))
      (node (ref "U1") (pin "38") (pinfunction "GPIO1_38") (pintype "bidirectional"))
    )
    (net (code "60") (name "Net-(U1-GPIO2)") (class "Default")
      (node (ref "R11") (pin "2") (pinfunction "2_2") (pintype "passive"))
      (node (ref "U1") (pin "39") (pinfunction "GPIO2_39") (pintype "bidirectional"))
    )
    (net (code "61") (name "Net-(U1-S1)") (class "Default")
      (node (ref "R37") (pin "1") (pinfunction "1_1") (pintype "passive"))
      (node (ref "U1") (pin "28") (pinfunction "S1_28") (pintype "tri_state"))
    )
    (net (code "62") (name "Net-(U1-S2)") (class "Default")
      (node (ref "R35") (pin "1") (pinfunction "1_1") (pintype "passive"))
      (node (ref "U1") (pin "26") (pinfunction "S2_26") (pintype "tri_state"))
    )
    (net (code "63") (name "Net-(U1-S3)") (class "Default")
      (node (ref "R33") (pin "1") (pinfunction "1_1") (pintype "passive"))
      (node (ref "U1") (pin "24") (pinfunction "S3_24") (pintype "tri_state"))
    )
    (net (code "64") (name "Net-(U1-S4)") (class "Default")
      (node (ref "R31") (pin "1") (pinfunction "1_1") (pintype "passive"))
      (node (ref "U1") (pin "22") (pinfunction "S4_22") (pintype "tri_state"))
    )
    (net (code "65") (name "Net-(U1-S5)") (class "Default")
      (node (ref "R29") (pin "1") (pinfunction "1_1") (pintype "passive"))
      (node (ref "U1") (pin "20") (pinfunction "S5_20") (pintype "tri_state"))
    )
    (net (code "66") (name "Net-(U1-S6)") (class "Default")
      (node (ref "R27") (pin "1") (pinfunction "1_1") (pintype "passive"))
      (node (ref "U1") (pin "18") (pinfunction "S6_18") (pintype "tri_state"))
    )
    (net (code "67") (name "Net-(U1-S7)") (class "Default")
      (node (ref "R25") (pin "1") (pinfunction "1_1") (pintype "passive"))
      (node (ref "U1") (pin "16") (pinfunction "S7_16") (pintype "tri_state"))
    )
    (net (code "68") (name "Net-(U1-S8)") (class "Default")
      (node (ref "R23") (pin "1") (pinfunction "1_1") (pintype "passive"))
      (node (ref "U1") (pin "14") (pinfunction "S8_14") (pintype "tri_state"))
    )
    (net (code "69") (name "Net-(U1-S9)") (class "Default")
      (node (ref "R21") (pin "1") (pinfunction "1_1") (pintype "passive"))
      (node (ref "U1") (pin "12") (pinfunction "S9_12") (pintype "tri_state"))
    )
    (net (code "70") (name "Net-(U1-S10)") (class "Default")
      (node (ref "R19") (pin "1") (pinfunction "1_1") (pintype "passive"))
      (node (ref "U1") (pin "10") (pinfunction "S10_10") (pintype "tri_state"))
    )
    (net (code "71") (name "Net-(U1-S11)") (class "Default")
      (node (ref "R17") (pin "1") (pinfunction "1_1") (pintype "passive"))
      (node (ref "U1") (pin "8") (pinfunction "S11_8") (pintype "tri_state"))
    )
    (net (code "72") (name "Net-(U1-S12)") (class "Default")
      (node (ref "R15") (pin "1") (pinfunction "1_1") (pintype "passive"))
      (node (ref "U1") (pin "6") (pinfunction "S12_6") (pintype "tri_state"))
    )
    (net (code "73") (name "Net-(U1-V+)") (class "Default")
      (node (ref "C2") (pin "2") (pinfunction "2_2") (pintype "passive"))
      (node (ref "R10") (pin "1") (pinfunction "1_1") (pintype "passive"))
      (node (ref "U1") (pin "4") (pinfunction "V+_4") (pintype "power_in"))
    )
    (net (code "74") (name "Net-(U1-VREF)") (class "Default")
      (node (ref "C5") (pin "2") (pinfunction "2_2") (pintype "passive"))
      (node (ref "R8") (pin "2") (pinfunction "2_2") (pintype "passive"))
      (node (ref "R9") (pin "2") (pinfunction "2_2") (pintype "passive"))
      (node (ref "U1") (pin "34") (pinfunction "VREF_34") (pintype "output"))
    )
    (net (code "75") (name "Net-(U1-WDTB)") (class "Default")
      (node (ref "R12") (pin "2") (pinfunction "2_2") (pintype "passive"))
      (node (ref "U1") (pin "37") (pinfunction "WDTB_37") (pintype "open_collector"))
    )
    (net (code "76") (name "VDD") (class "Default")
      (node (ref "L1") (pin "1") (pinfunction "1_1") (pintype "passive"))
    )
    (net (code "77") (name "unconnected-(U1-CSBO-Pad1)") (class "Default")
      (node (ref "U1") (pin "1") (pinfunction "CSBO_1") (pintype "output+no_connect"))
    )
    (net (code "78") (name "unconnected-(U1-SCKO-Pad3)") (class "Default")
      (node (ref "U1") (pin "3") (pinfunction "SCKO_3") (pintype "output+no_connect"))
    )
    (net (code "79") (name "unconnected-(U1-SDOI-Pad2)") (class "Default")
      (node (ref "U1") (pin "2") (pinfunction "SDOI_2") (pintype "bidirectional+no_connect"))
    )
  )
)
